# junyabadge.net
KiCad netlist of a schematic drawn in EasyEDA Pro
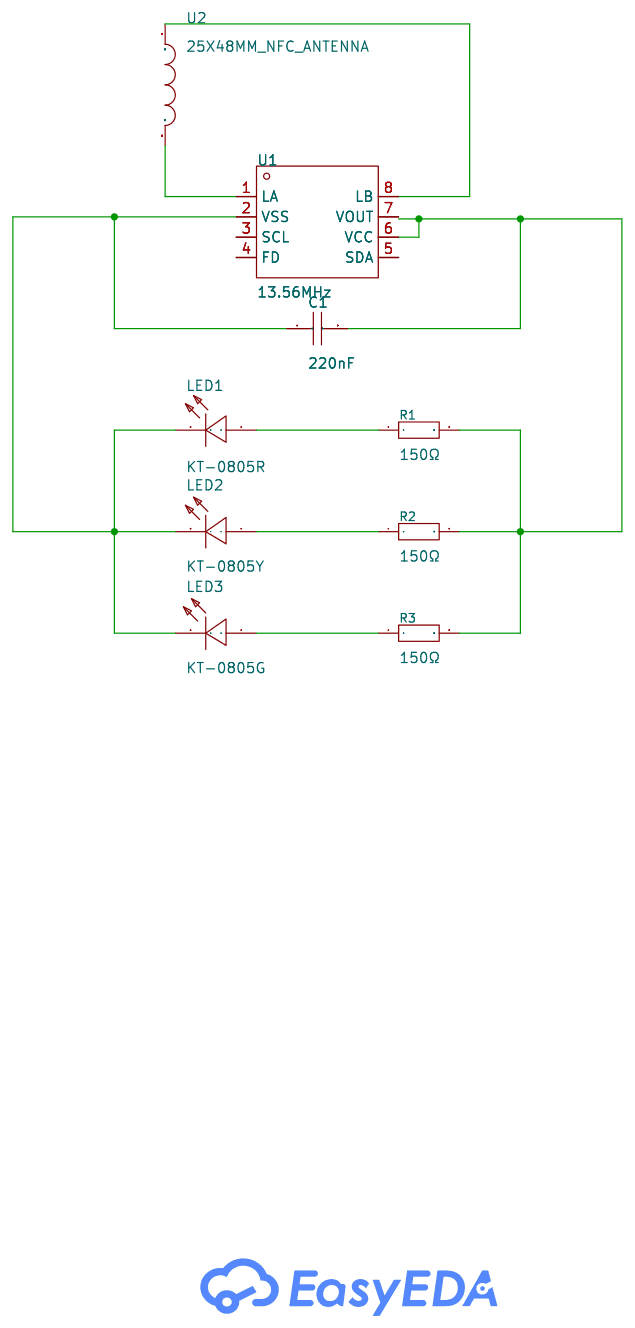
[diagram p0: schematic sheet]

(export (version "E")
  (design (tool "Eeschema 10.0.6"))
  (components
    (comp (ref "C1")
      (value "220nF")
      (footprint "easyedapro:C0603")
      (fields
        (field (name "Manufacturer Part") "CL10B224KA8NNNC")
        (field (name "Manufacturer") "SAMSUNG(三星)")
      )
      (libsource (lib "easyedapro") (part "CL10B224KA8NNNC"))
    )
    (comp (ref "LED1")
      (value "KT-0805R")
      (footprint "easyedapro:LED0805-R-RD")
      (fields (field (name "Manufacturer") "KENTO"))
      (libsource (lib "easyedapro") (part "E6C0805UR"))
    )
    (comp (ref "LED2")
      (value "KT-0805Y")
      (footprint "easyedapro:LED0805-R-RD")
      (fields (field (name "Manufacturer") "KENTO"))
      (libsource (lib "easyedapro") (part "17-21SUYC/TR8"))
    )
    (comp (ref "LED3")
      (value "KT-0805G")
      (footprint "easyedapro:LED0805-R-RD")
      (fields (field (name "Manufacturer") "KENTO"))
      (libsource (lib "easyedapro") (part "0805G (Green)"))
    )
    (comp (ref "R1")
      (value "150Ω")
      (footprint "easyedapro:R0603")
      (fields
        (field (name "Manufacturer Part") "0603WAF1500T5E")
        (field (name "Manufacturer") "UNI-ROYAL(厚声)")
      )
      (libsource (lib "easyedapro") (part "0603WAF1500T5E"))
    )
    (comp (ref "R2")
      (value "150Ω")
      (footprint "easyedapro:R0603")
      (fields
        (field (name "Manufacturer Part") "0603WAF1500T5E")
        (field (name "Manufacturer") "UNI-ROYAL(厚声)")
      )
      (libsource (lib "easyedapro") (part "0603WAF1500T5E"))
    )
    (comp (ref "R3")
      (value "150Ω")
      (footprint "easyedapro:R0603")
      (fields
        (field (name "Manufacturer Part") "0603WAF1500T5E")
        (field (name "Manufacturer") "UNI-ROYAL(厚声)")
      )
      (libsource (lib "easyedapro") (part "0603WAF1500T5E"))
    )
    (comp (ref "U1")
      (value "13.56MHz")
      (footprint "easyedapro:XQFN-8_L1.6-W1.6-P0.50-BL_NT3H2111W0FHKH")
      (fields (field (name "Manufacturer Part") "NT3H2111W0FHKH") (field (name "Manufacturer") "NXP(恩智浦)"))
      (libsource (lib "easyedapro") (part "NT3H2111W0FHKH"))
    )
    (comp (ref "U2")
      (value "25X48MM_NFC_ANTENNA")
      (footprint "easyedapro:25X48MM_NFC_ANTENNA")
      (libsource (lib "easyedapro") (part "25X48MM_NFC_ANTENNA"))
    )
  )
  (nets
    (net (code "1") (name "Net-(LED1-A)") (class "Default")
      (node (ref "LED1") (pin "1") (pinfunction "A_1") (pintype "unspecified"))
      (node (ref "R1") (pin "1") (pinfunction "1_1") (pintype "input"))
    )
    (net (code "2") (name "Net-(LED1-K)") (class "Default")
      (node (ref "C1") (pin "1") (pinfunction "1_1") (pintype "input"))
      (node (ref "LED1") (pin "2") (pinfunction "K_2") (pintype "unspecified"))
      (node (ref "LED2") (pin "2") (pinfunction "-_2") (pintype "unspecified"))
      (node (ref "LED3") (pin "2") (pinfunction "K_2") (pintype "unspecified"))
      (node (ref "U1") (pin "2") (pinfunction "VSS_2") (pintype "unspecified"))
    )
    (net (code "3") (name "Net-(LED2-+)") (class "Default")
      (node (ref "LED2") (pin "1") (pinfunction "+_1") (pintype "unspecified"))
      (node (ref "R2") (pin "1") (pinfunction "1_1") (pintype "input"))
    )
    (net (code "4") (name "Net-(LED3-A)") (class "Default")
      (node (ref "LED3") (pin "1") (pinfunction "A_1") (pintype "unspecified"))
      (node (ref "R3") (pin "1") (pinfunction "1_1") (pintype "input"))
    )
    (net (code "5") (name "Net-(U1-LA)") (class "Default")
      (node (ref "U1") (pin "1") (pinfunction "LA_1") (pintype "unspecified"))
      (node (ref "U2") (pin "P$2") (pinfunction "P$2_P$2") (pintype "bidirectional"))
    )
    (net (code "6") (name "Net-(U1-LB)") (class "Default")
      (node (ref "U1") (pin "8") (pinfunction "LB_8") (pintype "unspecified"))
      (node (ref "U2") (pin "P$1") (pinfunction "P$1_P$1") (pintype "bidirectional"))
    )
    (net (code "7") (name "Net-(U1-VCC)") (class "Default")
      (node (ref "C1") (pin "2") (pinfunction "2_2") (pintype "input"))
      (node (ref "R1") (pin "2") (pinfunction "2_2") (pintype "input"))
      (node (ref "R2") (pin "2") (pinfunction "2_2") (pintype "input"))
      (node (ref "R3") (pin "2") (pinfunction "2_2") (pintype "input"))
      (node (ref "U1") (pin "6") (pinfunction "VCC_6") (pintype "unspecified"))
    )
    (net (code "8") (name "unconnected-(U1-FD-Pad4)") (class "Default")
      (node (ref "U1") (pin "4") (pinfunction "FD_4") (pintype "unspecified"))
    )
    (net (code "9") (name "unconnected-(U1-SCL-Pad3)") (class "Default")
      (node (ref "U1") (pin "3") (pinfunction "SCL_3") (pintype "unspecified"))
    )
    (net (code "10") (name "unconnected-(U1-SDA-Pad5)") (class "Default")
      (node (ref "U1") (pin "5") (pinfunction "SDA_5") (pintype "unspecified"))
    )
    (net (code "11") (name "unconnected-(U1-VOUT-Pad7)") (class "Default")
      (node (ref "U1") (pin "7") (pinfunction "VOUT_7") (pintype "unspecified"))
    )
  )
)
